# 8_ESP32.net
KiCad netlist of a schematic drawn in Altium Designer
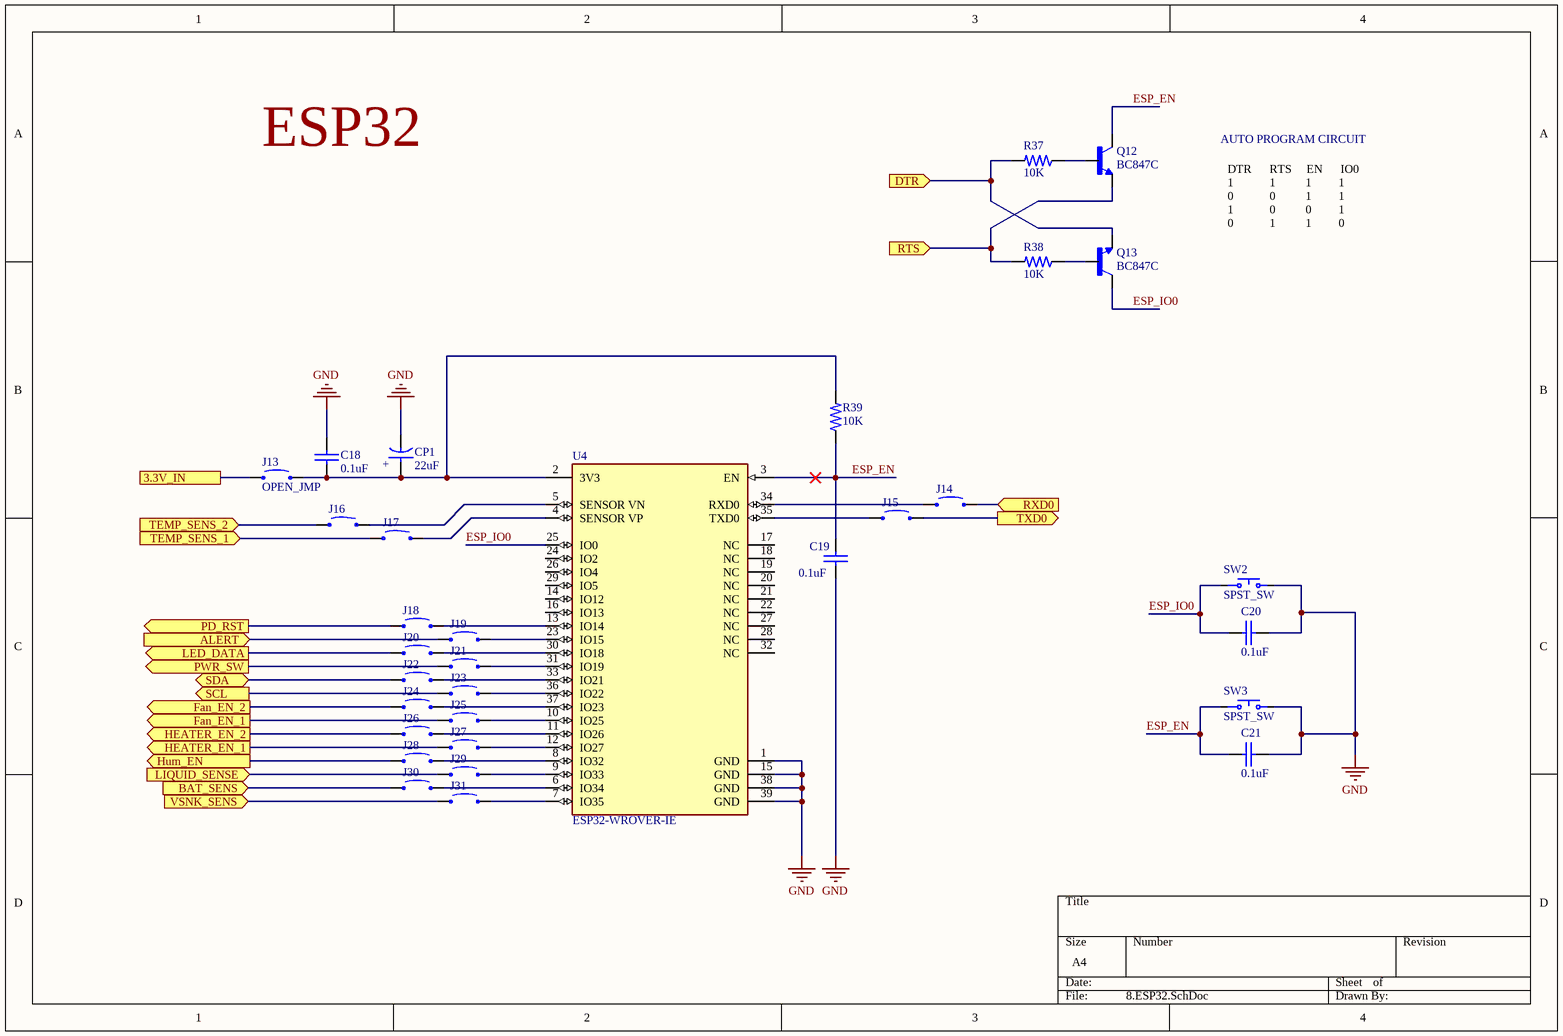
[diagram p0: 8.ESP32.SchDoc]

(export (version "E")
  (design (tool "Eeschema 10.0.6"))
  (components
    (comp (ref "C18") (value "0.1uF") (footprint "PcbLib:C_0603") (libsource (lib "Schlib") (part "C_0603")))
    (comp (ref "C19") (value "0.1uF") (footprint "PcbLib:C_0603") (libsource (lib "Schlib") (part "C_0603")))
    (comp (ref "C20") (value "0.1uF") (footprint "PcbLib:C_0603") (libsource (lib "Schlib") (part "C_0603")))
    (comp (ref "C21") (value "0.1uF") (footprint "PcbLib:C_0603") (libsource (lib "Schlib") (part "C_0603")))
    (comp (ref "CP1") (value "22uF") (libsource (lib "Schlib") (part "CP")))
    (comp (ref "J13")
      (value "OPEN_JMP")
      (footprint "PcbLib:OPEN_JMP")
      (libsource (lib "Schlib") (part "OPEN_JMP"))
    )
    (comp (ref "J14")
      (value "OPEN_JMP")
      (footprint "PcbLib:OPEN_JMP")
      (libsource (lib "Schlib") (part "OPEN_JMP"))
    )
    (comp (ref "J15")
      (value "OPEN_JMP")
      (footprint "PcbLib:OPEN_JMP")
      (libsource (lib "Schlib") (part "OPEN_JMP"))
    )
    (comp (ref "J16")
      (value "OPEN_JMP")
      (footprint "PcbLib:OPEN_JMP")
      (libsource (lib "Schlib") (part "OPEN_JMP"))
    )
    (comp (ref "J17")
      (value "OPEN_JMP")
      (footprint "PcbLib:OPEN_JMP")
      (libsource (lib "Schlib") (part "OPEN_JMP"))
    )
    (comp (ref "J18")
      (value "OPEN_JMP")
      (footprint "PcbLib:OPEN_JMP")
      (libsource (lib "Schlib") (part "OPEN_JMP"))
    )
    (comp (ref "J19")
      (value "OPEN_JMP")
      (footprint "PcbLib:OPEN_JMP")
      (libsource (lib "Schlib") (part "OPEN_JMP"))
    )
    (comp (ref "J20")
      (value "OPEN_JMP")
      (footprint "PcbLib:OPEN_JMP")
      (libsource (lib "Schlib") (part "OPEN_JMP"))
    )
    (comp (ref "J21")
      (value "OPEN_JMP")
      (footprint "PcbLib:OPEN_JMP")
      (libsource (lib "Schlib") (part "OPEN_JMP"))
    )
    (comp (ref "J22")
      (value "OPEN_JMP")
      (footprint "PcbLib:OPEN_JMP")
      (libsource (lib "Schlib") (part "OPEN_JMP"))
    )
    (comp (ref "J23")
      (value "OPEN_JMP")
      (footprint "PcbLib:OPEN_JMP")
      (libsource (lib "Schlib") (part "OPEN_JMP"))
    )
    (comp (ref "J24")
      (value "OPEN_JMP")
      (footprint "PcbLib:OPEN_JMP")
      (libsource (lib "Schlib") (part "OPEN_JMP"))
    )
    (comp (ref "J25")
      (value "OPEN_JMP")
      (footprint "PcbLib:OPEN_JMP")
      (libsource (lib "Schlib") (part "OPEN_JMP"))
    )
    (comp (ref "J26")
      (value "OPEN_JMP")
      (footprint "PcbLib:OPEN_JMP")
      (libsource (lib "Schlib") (part "OPEN_JMP"))
    )
    (comp (ref "J27")
      (value "OPEN_JMP")
      (footprint "PcbLib:OPEN_JMP")
      (libsource (lib "Schlib") (part "OPEN_JMP"))
    )
    (comp (ref "J28")
      (value "OPEN_JMP")
      (footprint "PcbLib:OPEN_JMP")
      (libsource (lib "Schlib") (part "OPEN_JMP"))
    )
    (comp (ref "J29")
      (value "OPEN_JMP")
      (footprint "PcbLib:OPEN_JMP")
      (libsource (lib "Schlib") (part "OPEN_JMP"))
    )
    (comp (ref "J30")
      (value "OPEN_JMP")
      (footprint "PcbLib:OPEN_JMP")
      (libsource (lib "Schlib") (part "OPEN_JMP"))
    )
    (comp (ref "J31")
      (value "OPEN_JMP")
      (footprint "PcbLib:OPEN_JMP")
      (libsource (lib "Schlib") (part "OPEN_JMP"))
    )
    (comp (ref "Q12")
      (value "BC847C")
      (footprint "SOT-23-3")
      (fields (field (name "MFR") "Nexperia"))
      (libsource (lib "") (part "BC847C_1"))
    )
    (comp (ref "Q13")
      (value "BC847C")
      (footprint "SOT-23-3")
      (fields (field (name "MFR") "Nexperia"))
      (libsource (lib "Schlib") (part "BC847C"))
    )
    (comp (ref "R37") (value "10K") (footprint "R_0603") (libsource (lib "Schlib") (part "R_0603")))
    (comp (ref "R38") (value "10K") (footprint "R_0603") (libsource (lib "Schlib") (part "R_0603")))
    (comp (ref "R39") (value "10K") (footprint "R_0603") (libsource (lib "Schlib") (part "R_0603")))
    (comp (ref "SW2")
      (value "SPST_SW")
      (footprint "PTS636 SM43J SMTR LFS")
      (fields (field (name "MFR") "C&K"))
      (libsource (lib "Schlib") (part "SPST_SW"))
    )
    (comp (ref "SW3")
      (value "SPST_SW")
      (footprint "PTS636 SM43J SMTR LFS")
      (fields (field (name "MFR") "C&K"))
      (libsource (lib "Schlib") (part "SPST_SW"))
    )
    (comp (ref "U4")
      (value "ESP32-WROVER-IE")
      (footprint "PcbLib:ESP32-WROVER-IE")
      (fields (field (name "MFR") "Espressif Systems"))
      (libsource (lib "Schlib") (part "ESP32-WROVER-IE"))
    )
  )
  (nets
    (net (code "1") (name "/3.3V_IN") (class "Default")
      (node (ref "J13") (pin "1") (pinfunction "1_1") (pintype "passive"))
    )
    (net (code "2") (name "/ALERT") (class "Default")
      (node (ref "J19") (pin "1") (pinfunction "1_1") (pintype "passive"))
    )
    (net (code "3") (name "/BAT_SENS") (class "Default")
      (node (ref "J30") (pin "1") (pinfunction "1_1") (pintype "passive"))
    )
    (net (code "4") (name "/DTR") (class "Default")
      (node (ref "Q13") (pin "2") (pinfunction "E_2") (pintype "passive"))
      (node (ref "R37") (pin "2") (pinfunction "2_2") (pintype "passive"))
    )
    (net (code "5") (name "/ESP_EN") (class "Default")
      (node (ref "C19") (pin "2") (pinfunction "2_2") (pintype "passive"))
      (node (ref "C21") (pin "2") (pinfunction "2_2") (pintype "passive"))
      (node (ref "Q12") (pin "3") (pinfunction "C_3") (pintype "passive"))
      (node (ref "R39") (pin "1") (pinfunction "1_1") (pintype "passive"))
      (node (ref "SW3") (pin "1") (pinfunction "COM_1") (pintype "passive"))
      (node (ref "U4") (pin "3") (pinfunction "EN_3") (pintype "input"))
    )
    (net (code "6") (name "/ESP_IO0") (class "Default")
      (node (ref "C20") (pin "2") (pinfunction "2_2") (pintype "passive"))
      (node (ref "Q13") (pin "3") (pinfunction "C_3") (pintype "passive"))
      (node (ref "SW2") (pin "1") (pinfunction "COM_1") (pintype "passive"))
      (node (ref "U4") (pin "25") (pinfunction "IO0_25") (pintype "bidirectional"))
    )
    (net (code "7") (name "/Fan_EN_1") (class "Default")
      (node (ref "J25") (pin "1") (pinfunction "1_1") (pintype "passive"))
    )
    (net (code "8") (name "/Fan_EN_2") (class "Default")
      (node (ref "J24") (pin "1") (pinfunction "1_1") (pintype "passive"))
    )
    (net (code "9") (name "/HEATER_EN_1") (class "Default")
      (node (ref "J27") (pin "1") (pinfunction "1_1") (pintype "passive"))
    )
    (net (code "10") (name "/HEATER_EN_2") (class "Default")
      (node (ref "J26") (pin "1") (pinfunction "1_1") (pintype "passive"))
    )
    (net (code "11") (name "/Hum_EN") (class "Default")
      (node (ref "J28") (pin "1") (pinfunction "1_1") (pintype "passive"))
    )
    (net (code "12") (name "/LED_DATA") (class "Default")
      (node (ref "J20") (pin "1") (pinfunction "1_1") (pintype "passive"))
    )
    (net (code "13") (name "/LIQUID_SENSE") (class "Default")
      (node (ref "J29") (pin "1") (pinfunction "1_1") (pintype "passive"))
    )
    (net (code "14") (name "/PD_RST") (class "Default")
      (node (ref "J18") (pin "1") (pinfunction "1_1") (pintype "passive"))
    )
    (net (code "15") (name "/PWR_SW") (class "Default")
      (node (ref "J21") (pin "1") (pinfunction "1_1") (pintype "passive"))
    )
    (net (code "16") (name "/RTS") (class "Default")
      (node (ref "Q12") (pin "2") (pinfunction "E_2") (pintype "passive"))
      (node (ref "R38") (pin "2") (pinfunction "2_2") (pintype "passive"))
    )
    (net (code "17") (name "/RXD0") (class "Default")
      (node (ref "J14") (pin "2") (pinfunction "2_2") (pintype "passive"))
    )
    (net (code "18") (name "/SCL") (class "Default")
      (node (ref "J23") (pin "1") (pinfunction "1_1") (pintype "passive"))
    )
    (net (code "19") (name "/SDA") (class "Default")
      (node (ref "J22") (pin "1") (pinfunction "1_1") (pintype "passive"))
    )
    (net (code "20") (name "/TEMP_SENS_1") (class "Default")
      (node (ref "J17") (pin "1") (pinfunction "1_1") (pintype "passive"))
    )
    (net (code "21") (name "/TEMP_SENS_2") (class "Default")
      (node (ref "J16") (pin "1") (pinfunction "1_1") (pintype "passive"))
    )
    (net (code "22") (name "/TXD0") (class "Default")
      (node (ref "J15") (pin "2") (pinfunction "2_2") (pintype "passive"))
    )
    (net (code "23") (name "/VSNK_SENS") (class "Default")
      (node (ref "J31") (pin "1") (pinfunction "1_1") (pintype "passive"))
    )
    (net (code "24") (name "GND") (class "Default")
      (node (ref "C18") (pin "2") (pinfunction "2_2") (pintype "passive"))
      (node (ref "C19") (pin "1") (pinfunction "1_1") (pintype "passive"))
      (node (ref "C20") (pin "1") (pinfunction "1_1") (pintype "passive"))
      (node (ref "C21") (pin "1") (pinfunction "1_1") (pintype "passive"))
      (node (ref "CP1") (pin "2") (pinfunction "2_2") (pintype "passive"))
      (node (ref "SW2") (pin "2") (pinfunction "NO_2") (pintype "passive"))
      (node (ref "SW3") (pin "2") (pinfunction "NO_2") (pintype "passive"))
      (node (ref "U4") (pin "1") (pinfunction "GND_1") (pintype "power_in"))
      (node (ref "U4") (pin "15") (pinfunction "GND_15") (pintype "power_in"))
      (node (ref "U4") (pin "38") (pinfunction "GND_38") (pintype "power_in"))
      (node (ref "U4") (pin "39") (pinfunction "GND_39") (pintype "power_in"))
    )
    (net (code "25") (name "Net-(Q12-B)") (class "Default")
      (node (ref "Q12") (pin "1") (pinfunction "B_1") (pintype "passive"))
      (node (ref "R37") (pin "1") (pinfunction "1_1") (pintype "passive"))
    )
    (net (code "26") (name "Net-(Q13-B)") (class "Default")
      (node (ref "Q13") (pin "1") (pinfunction "B_1") (pintype "passive"))
      (node (ref "R38") (pin "1") (pinfunction "1_1") (pintype "passive"))
    )
    (net (code "27") (name "Net-(U4-3V3)") (class "Default")
      (node (ref "C18") (pin "1") (pinfunction "1_1") (pintype "passive"))
      (node (ref "CP1") (pin "1") (pinfunction "1_1") (pintype "passive"))
      (node (ref "J13") (pin "2") (pinfunction "2_2") (pintype "passive"))
      (node (ref "R39") (pin "2") (pinfunction "2_2") (pintype "passive"))
      (node (ref "U4") (pin "2") (pinfunction "3V3_2") (pintype "power_in"))
    )
    (net (code "28") (name "Net-(U4-IO14)") (class "Default")
      (node (ref "J18") (pin "2") (pinfunction "2_2") (pintype "passive"))
      (node (ref "U4") (pin "13") (pinfunction "IO14_13") (pintype "bidirectional"))
    )
    (net (code "29") (name "Net-(U4-IO15)") (class "Default")
      (node (ref "J19") (pin "2") (pinfunction "2_2") (pintype "passive"))
      (node (ref "U4") (pin "23") (pinfunction "IO15_23") (pintype "bidirectional"))
    )
    (net (code "30") (name "Net-(U4-IO18)") (class "Default")
      (node (ref "J20") (pin "2") (pinfunction "2_2") (pintype "passive"))
      (node (ref "U4") (pin "30") (pinfunction "IO18_30") (pintype "bidirectional"))
    )
    (net (code "31") (name "Net-(U4-IO19)") (class "Default")
      (node (ref "J21") (pin "2") (pinfunction "2_2") (pintype "passive"))
      (node (ref "U4") (pin "31") (pinfunction "IO19_31") (pintype "bidirectional"))
    )
    (net (code "32") (name "Net-(U4-IO21)") (class "Default")
      (node (ref "J22") (pin "2") (pinfunction "2_2") (pintype "passive"))
      (node (ref "U4") (pin "33") (pinfunction "IO21_33") (pintype "bidirectional"))
    )
    (net (code "33") (name "Net-(U4-IO22)") (class "Default")
      (node (ref "J23") (pin "2") (pinfunction "2_2") (pintype "passive"))
      (node (ref "U4") (pin "36") (pinfunction "IO22_36") (pintype "bidirectional"))
    )
    (net (code "34") (name "Net-(U4-IO23)") (class "Default")
      (node (ref "J24") (pin "2") (pinfunction "2_2") (pintype "passive"))
      (node (ref "U4") (pin "37") (pinfunction "IO23_37") (pintype "bidirectional"))
    )
    (net (code "35") (name "Net-(U4-IO25)") (class "Default")
      (node (ref "J25") (pin "2") (pinfunction "2_2") (pintype "passive"))
      (node (ref "U4") (pin "10") (pinfunction "IO25_10") (pintype "bidirectional"))
    )
    (net (code "36") (name "Net-(U4-IO26)") (class "Default")
      (node (ref "J26") (pin "2") (pinfunction "2_2") (pintype "passive"))
      (node (ref "U4") (pin "11") (pinfunction "IO26_11") (pintype "bidirectional"))
    )
    (net (code "37") (name "Net-(U4-IO27)") (class "Default")
      (node (ref "J27") (pin "2") (pinfunction "2_2") (pintype "passive"))
      (node (ref "U4") (pin "12") (pinfunction "IO27_12") (pintype "bidirectional"))
    )
    (net (code "38") (name "Net-(U4-IO32)") (class "Default")
      (node (ref "J28") (pin "2") (pinfunction "2_2") (pintype "passive"))
      (node (ref "U4") (pin "8") (pinfunction "IO32_8") (pintype "bidirectional"))
    )
    (net (code "39") (name "Net-(U4-IO33)") (class "Default")
      (node (ref "J29") (pin "2") (pinfunction "2_2") (pintype "passive"))
      (node (ref "U4") (pin "9") (pinfunction "IO33_9") (pintype "bidirectional"))
    )
    (net (code "40") (name "Net-(U4-IO34)") (class "Default")
      (node (ref "J30") (pin "2") (pinfunction "2_2") (pintype "passive"))
      (node (ref "U4") (pin "6") (pinfunction "IO34_6") (pintype "bidirectional"))
    )
    (net (code "41") (name "Net-(U4-IO35)") (class "Default")
      (node (ref "J31") (pin "2") (pinfunction "2_2") (pintype "passive"))
      (node (ref "U4") (pin "7") (pinfunction "IO35_7") (pintype "bidirectional"))
    )
    (net (code "42") (name "Net-(U4-RXD0)") (class "Default")
      (node (ref "J14") (pin "1") (pinfunction "1_1") (pintype "passive"))
      (node (ref "U4") (pin "34") (pinfunction "RXD0_34") (pintype "bidirectional"))
    )
    (net (code "43") (name "Net-(U4-SENSOR_VN)") (class "Default")
      (node (ref "J16") (pin "2") (pinfunction "2_2") (pintype "passive"))
      (node (ref "U4") (pin "5") (pinfunction "SENSOR_VN_5") (pintype "bidirectional"))
    )
    (net (code "44") (name "Net-(U4-SENSOR_VP)") (class "Default")
      (node (ref "J17") (pin "2") (pinfunction "2_2") (pintype "passive"))
      (node (ref "U4") (pin "4") (pinfunction "SENSOR_VP_4") (pintype "bidirectional"))
    )
    (net (code "45") (name "Net-(U4-TXD0)") (class "Default")
      (node (ref "J15") (pin "1") (pinfunction "1_1") (pintype "passive"))
      (node (ref "U4") (pin "35") (pinfunction "TXD0_35") (pintype "bidirectional"))
    )
    (net (code "46") (name "unconnected-(U4-IO2-Pad24)") (class "Default")
      (node (ref "U4") (pin "24") (pinfunction "IO2_24") (pintype "bidirectional"))
    )
    (net (code "47") (name "unconnected-(U4-IO4-Pad26)") (class "Default")
      (node (ref "U4") (pin "26") (pinfunction "IO4_26") (pintype "bidirectional"))
    )
    (net (code "48") (name "unconnected-(U4-IO5-Pad29)") (class "Default")
      (node (ref "U4") (pin "29") (pinfunction "IO5_29") (pintype "bidirectional"))
    )
    (net (code "49") (name "unconnected-(U4-IO12-Pad14)") (class "Default")
      (node (ref "U4") (pin "14") (pinfunction "IO12_14") (pintype "bidirectional"))
    )
    (net (code "50") (name "unconnected-(U4-IO13-Pad16)") (class "Default")
      (node (ref "U4") (pin "16") (pinfunction "IO13_16") (pintype "bidirectional"))
    )
    (net (code "51") (name "unconnected-(U4-NC-Pad17)") (class "Default")
      (node (ref "U4") (pin "17") (pinfunction "NC_17") (pintype "passive"))
    )
    (net (code "52") (name "unconnected-(U4-NC-Pad18)") (class "Default")
      (node (ref "U4") (pin "18") (pinfunction "NC_18") (pintype "passive"))
    )
    (net (code "53") (name "unconnected-(U4-NC-Pad19)") (class "Default")
      (node (ref "U4") (pin "19") (pinfunction "NC_19") (pintype "passive"))
    )
    (net (code "54") (name "unconnected-(U4-NC-Pad20)") (class "Default")
      (node (ref "U4") (pin "20") (pinfunction "NC_20") (pintype "passive"))
    )
    (net (code "55") (name "unconnected-(U4-NC-Pad21)") (class "Default")
      (node (ref "U4") (pin "21") (pinfunction "NC_21") (pintype "passive"))
    )
    (net (code "56") (name "unconnected-(U4-NC-Pad22)") (class "Default")
      (node (ref "U4") (pin "22") (pinfunction "NC_22") (pintype "passive"))
    )
    (net (code "57") (name "unconnected-(U4-NC-Pad27)") (class "Default")
      (node (ref "U4") (pin "27") (pinfunction "NC_27") (pintype "passive"))
    )
    (net (code "58") (name "unconnected-(U4-NC-Pad28)") (class "Default")
      (node (ref "U4") (pin "28") (pinfunction "NC_28") (pintype "passive"))
    )
    (net (code "59") (name "unconnected-(U4-NC-Pad32)") (class "Default")
      (node (ref "U4") (pin "32") (pinfunction "NC_32") (pintype "passive"))
    )
  )
)
